# max6_breakout_lcv3.net
KiCad netlist of a schematic drawn in EAGLE
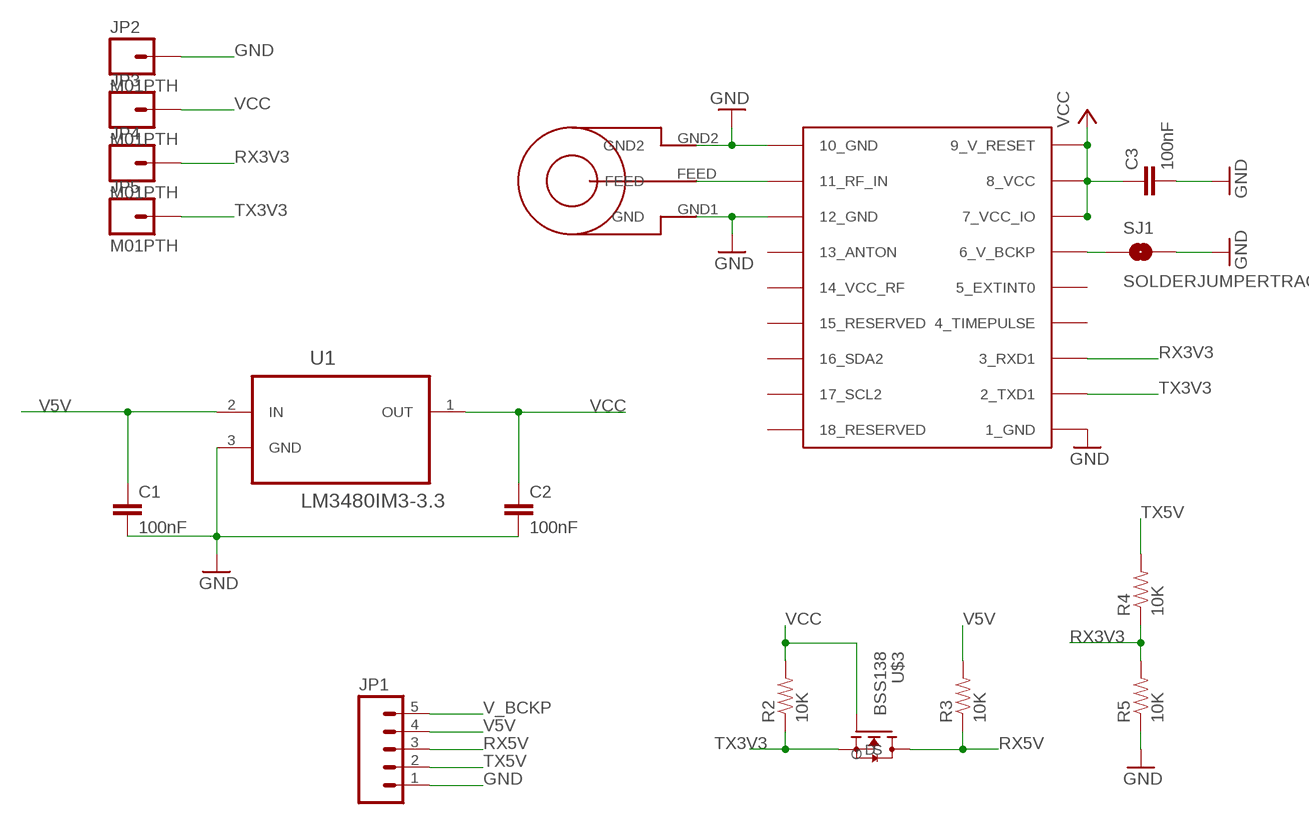
[diagram p0: schematic, sheet 1]

(export (version "E")
  (design (tool "Eeschema 10.0.6"))
  (components
    (comp (ref "C1")
      (value "100nF")
      (footprint "eagle-import:0603-CAP")
      (libsource (lib "eagle-import") (part "CAP0603-CAP"))
    )
    (comp (ref "C2")
      (value "100nF")
      (footprint "eagle-import:0603-CAP")
      (libsource (lib "eagle-import") (part "CAP0603-CAP"))
    )
    (comp (ref "C3")
      (value "100nF")
      (footprint "eagle-import:0603-CAP")
      (libsource (lib "eagle-import") (part "CAP0603-CAP"))
    )
    (comp (ref "JP1")
      (value "M05PTH")
      (footprint "eagle-import:1X05")
      (libsource (lib "eagle-import") (part "M05PTH"))
    )
    (comp (ref "JP2")
      (value "M01PTH")
      (footprint "eagle-import:1X01")
      (libsource (lib "eagle-import") (part "M01PTH"))
    )
    (comp (ref "JP3")
      (value "M01PTH")
      (footprint "eagle-import:1X01")
      (libsource (lib "eagle-import") (part "M01PTH"))
    )
    (comp (ref "JP4")
      (value "M01PTH")
      (footprint "eagle-import:1X01")
      (libsource (lib "eagle-import") (part "M01PTH"))
    )
    (comp (ref "JP5")
      (value "M01PTH")
      (footprint "eagle-import:1X01")
      (libsource (lib "eagle-import") (part "M01PTH"))
    )
    (comp (ref "R2")
      (value "10K")
      (footprint "eagle-import:0603-RES")
      (libsource (lib "eagle-import") (part "RESISTOR0603-RES"))
    )
    (comp (ref "R3")
      (value "10K")
      (footprint "eagle-import:0603-RES")
      (libsource (lib "eagle-import") (part "RESISTOR0603-RES"))
    )
    (comp (ref "R4")
      (value "10K")
      (footprint "eagle-import:0603-RES")
      (libsource (lib "eagle-import") (part "RESISTOR0603-RES"))
    )
    (comp (ref "R5")
      (value "10K")
      (footprint "eagle-import:0603-RES")
      (libsource (lib "eagle-import") (part "RESISTOR0603-RES"))
    )
    (comp (ref "SJ1")
      (value "SOLDERJUMPERTRACE")
      (footprint "eagle-import:SJ_2S-TRACE")
      (libsource (lib "eagle-import") (part "SOLDERJUMPERTRACE"))
    )
    (comp (ref "U$1")
      (value "UBLOX_MAX-6")
      (footprint "eagle-import:UBLOX_MAX-6")
      (libsource (lib "eagle-import") (part "UBLOX_MAX-6"))
    )
    (comp (ref "U$2")
      (value "SARANTEL-SR1202")
      (footprint "eagle-import:SARANTEL-SR1202")
      (libsource (lib "eagle-import") (part "SARANTEL-SR1202"))
    )
    (comp (ref "U$3")
      (value "BSS138")
      (footprint "eagle-import:BSS138")
      (libsource (lib "eagle-import") (part "BSS138"))
    )
    (comp (ref "U1")
      (value "LM3480IM3-3.3")
      (footprint "eagle-import:SOT95P251X112-3N")
      (libsource (lib "eagle-import") (part "LM3480IM3-3.3"))
    )
  )
  (nets
    (net (code "1") (name "/RX3V3") (class "Default")
      (node (ref "JP4") (pin "1") (pinfunction "1_1") (pintype "passive"))
      (node (ref "R4") (pin "1") (pinfunction "1_1") (pintype "passive"))
      (node (ref "R5") (pin "2") (pinfunction "2_2") (pintype "passive"))
      (node (ref "U$1") (pin "3_RXD1") (pinfunction "3_RXD1_3_RXD1") (pintype "bidirectional"))
    )
    (net (code "2") (name "/RX5V") (class "Default")
      (node (ref "JP1") (pin "3") (pinfunction "3_3") (pintype "passive"))
      (node (ref "R3") (pin "1") (pinfunction "1_1") (pintype "passive"))
      (node (ref "U$3") (pin "D") (pinfunction "D_D") (pintype "passive"))
    )
    (net (code "3") (name "/TX3V3") (class "Default")
      (node (ref "JP5") (pin "1") (pinfunction "1_1") (pintype "passive"))
      (node (ref "R2") (pin "1") (pinfunction "1_1") (pintype "passive"))
      (node (ref "U$1") (pin "2_TXD1") (pinfunction "2_TXD1_2_TXD1") (pintype "bidirectional"))
      (node (ref "U$3") (pin "S") (pinfunction "S_S") (pintype "passive"))
    )
    (net (code "4") (name "/TX5V") (class "Default")
      (node (ref "JP1") (pin "2") (pinfunction "2_2") (pintype "passive"))
      (node (ref "R4") (pin "2") (pinfunction "2_2") (pintype "passive"))
    )
    (net (code "5") (name "/V5V") (class "Default")
      (node (ref "C1") (pin "1") (pinfunction "1_1") (pintype "passive"))
      (node (ref "JP1") (pin "4") (pinfunction "4_4") (pintype "passive"))
      (node (ref "R3") (pin "2") (pinfunction "2_2") (pintype "passive"))
      (node (ref "U1") (pin "2") (pinfunction "IN_2") (pintype "power_in"))
    )
    (net (code "6") (name "/V_BCKP") (class "Default")
      (node (ref "JP1") (pin "5") (pinfunction "5_5") (pintype "passive"))
      (node (ref "SJ1") (pin "1") (pinfunction "1_1") (pintype "passive"))
      (node (ref "U$1") (pin "6_V_BCKP") (pinfunction "6_V_BCKP_6_V_BCKP") (pintype "bidirectional"))
    )
    (net (code "7") (name "GND") (class "Default")
      (node (ref "C1") (pin "2") (pinfunction "2_2") (pintype "passive"))
      (node (ref "C2") (pin "2") (pinfunction "2_2") (pintype "passive"))
      (node (ref "C3") (pin "2") (pinfunction "2_2") (pintype "passive"))
      (node (ref "JP1") (pin "1") (pinfunction "1_1") (pintype "passive"))
      (node (ref "JP2") (pin "1") (pinfunction "1_1") (pintype "passive"))
      (node (ref "R5") (pin "1") (pinfunction "1_1") (pintype "passive"))
      (node (ref "SJ1") (pin "2") (pinfunction "2_2") (pintype "passive"))
      (node (ref "U$1") (pin "10_GND") (pinfunction "10_GND_10_GND") (pintype "bidirectional"))
      (node (ref "U$1") (pin "12_GND") (pinfunction "12_GND_12_GND") (pintype "bidirectional"))
      (node (ref "U$1") (pin "1_GND") (pinfunction "1_GND_1_GND") (pintype "bidirectional"))
      (node (ref "U$2") (pin "GND1") (pinfunction "GND_GND1") (pintype "bidirectional"))
      (node (ref "U$2") (pin "GND2") (pinfunction "GND2_GND2") (pintype "bidirectional"))
      (node (ref "U1") (pin "3") (pinfunction "GND_3") (pintype "passive"))
    )
    (net (code "8") (name "Net-(U$1-Pad11_RF_IN)") (class "Default")
      (node (ref "U$1") (pin "11_RF_IN") (pinfunction "11_RF_IN_11_RF_IN") (pintype "bidirectional"))
      (node (ref "U$2") (pin "FEED") (pinfunction "FEED_FEED") (pintype "bidirectional"))
    )
    (net (code "9") (name "VCC") (class "Default")
      (node (ref "C2") (pin "1") (pinfunction "1_1") (pintype "passive"))
      (node (ref "C3") (pin "1") (pinfunction "1_1") (pintype "passive"))
      (node (ref "JP3") (pin "1") (pinfunction "1_1") (pintype "passive"))
      (node (ref "R2") (pin "2") (pinfunction "2_2") (pintype "passive"))
      (node (ref "U$1") (pin "7_VCC_IO") (pinfunction "7_VCC_IO_7_VCC_IO") (pintype "bidirectional"))
      (node (ref "U$1") (pin "8_VCC") (pinfunction "8_VCC_8_VCC") (pintype "bidirectional"))
      (node (ref "U$1") (pin "9_V_RESET") (pinfunction "9_V_RESET_9_V_RESET") (pintype "bidirectional"))
      (node (ref "U$3") (pin "G") (pinfunction "G_G") (pintype "passive"))
      (node (ref "U1") (pin "1") (pinfunction "OUT_1") (pintype "output"))
    )
    (net (code "10") (name "unconnected-(U$1-Pad4_TIMEPULSE)") (class "Default")
      (node (ref "U$1") (pin "4_TIMEPULSE") (pinfunction "4_TIMEPULSE_4_TIMEPULSE") (pintype "bidirectional"))
    )
    (net (code "11") (name "unconnected-(U$1-Pad5_EXTINT0)") (class "Default")
      (node (ref "U$1") (pin "5_EXTINT0") (pinfunction "5_EXTINT0_5_EXTINT0") (pintype "bidirectional"))
    )
    (net (code "12") (name "unconnected-(U$1-Pad13_ANTON)") (class "Default")
      (node (ref "U$1") (pin "13_ANTON") (pinfunction "13_ANTON_13_ANTON") (pintype "bidirectional"))
    )
    (net (code "13") (name "unconnected-(U$1-Pad14_VCC_RF)") (class "Default")
      (node (ref "U$1") (pin "14_VCC_RF") (pinfunction "14_VCC_RF_14_VCC_RF") (pintype "bidirectional"))
    )
    (net (code "14") (name "unconnected-(U$1-Pad15_RESERVED)") (class "Default")
      (node (ref "U$1") (pin "15_RESERVED") (pinfunction "15_RESERVED_15_RESERVED") (pintype "bidirectional"))
    )
    (net (code "15") (name "unconnected-(U$1-Pad16_SDA2)") (class "Default")
      (node (ref "U$1") (pin "16_SDA2") (pinfunction "16_SDA2_16_SDA2") (pintype "bidirectional"))
    )
    (net (code "16") (name "unconnected-(U$1-Pad17_SCL2)") (class "Default")
      (node (ref "U$1") (pin "17_SCL2") (pinfunction "17_SCL2_17_SCL2") (pintype "bidirectional"))
    )
    (net (code "17") (name "unconnected-(U$1-Pad18_RESERVED)") (class "Default")
      (node (ref "U$1") (pin "18_RESERVED") (pinfunction "18_RESERVED_18_RESERVED") (pintype "bidirectional"))
    )
  )
)
